# Choin_zlacza.net
KiCad netlist of a schematic drawn in Altium Designer
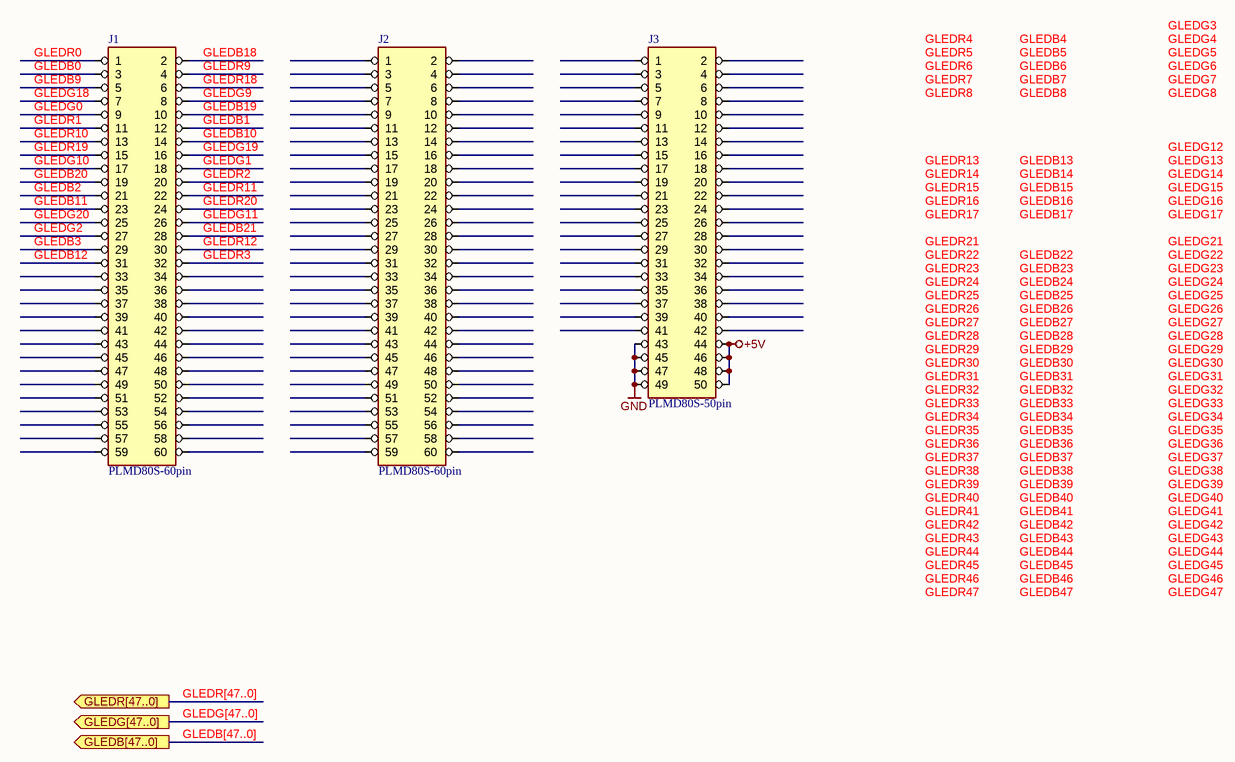
[diagram p0: Choin_zlacza.SchDoc]

(export (version "E")
  (design (tool "Eeschema 10.0.6"))
  (components
    (comp (ref "J1")
      (value "PLMD80S-60pin")
      (footprint "PLMD60S")
      (libsource (lib "Parts") (part "HEADER30X2"))
    )
    (comp (ref "J2")
      (value "PLMD80S-60pin")
      (footprint "PLMD60S")
      (libsource (lib "Parts") (part "HEADER30X2"))
    )
    (comp (ref "J3")
      (value "PLMD80S-50pin")
      (footprint "PLMD50S")
      (libsource (lib "Parts") (part "HEADER25X2"))
    )
  )
  (nets
    (net (code "1") (name "+5V") (class "Default")
      (node (ref "J3") (pin "44") (pinfunction "44_44") (pintype "passive"))
      (node (ref "J3") (pin "46") (pinfunction "46_46") (pintype "passive"))
      (node (ref "J3") (pin "48") (pinfunction "48_48") (pintype "passive"))
      (node (ref "J3") (pin "50") (pinfunction "50_50") (pintype "passive"))
    )
    (net (code "2") (name "/GLEDB0") (class "Default")
      (node (ref "J1") (pin "3") (pinfunction "3_3") (pintype "passive"))
    )
    (net (code "3") (name "/GLEDB1") (class "Default")
      (node (ref "J1") (pin "12") (pinfunction "12_12") (pintype "passive"))
    )
    (net (code "4") (name "/GLEDB2") (class "Default")
      (node (ref "J1") (pin "21") (pinfunction "21_21") (pintype "passive"))
    )
    (net (code "5") (name "/GLEDB3") (class "Default")
      (node (ref "J1") (pin "29") (pinfunction "29_29") (pintype "passive"))
    )
    (net (code "11") (name "/GLEDB9") (class "Default")
      (node (ref "J1") (pin "5") (pinfunction "5_5") (pintype "passive"))
    )
    (net (code "12") (name "/GLEDB10") (class "Default")
      (node (ref "J1") (pin "14") (pinfunction "14_14") (pintype "passive"))
    )
    (net (code "13") (name "/GLEDB11") (class "Default")
      (node (ref "J1") (pin "23") (pinfunction "23_23") (pintype "passive"))
    )
    (net (code "14") (name "/GLEDB12") (class "Default")
      (node (ref "J1") (pin "31") (pinfunction "31_31") (pintype "passive"))
    )
    (net (code "20") (name "/GLEDB18") (class "Default")
      (node (ref "J1") (pin "2") (pinfunction "2_2") (pintype "passive"))
    )
    (net (code "21") (name "/GLEDB19") (class "Default")
      (node (ref "J1") (pin "10") (pinfunction "10_10") (pintype "passive"))
    )
    (net (code "22") (name "/GLEDB20") (class "Default")
      (node (ref "J1") (pin "19") (pinfunction "19_19") (pintype "passive"))
    )
    (net (code "23") (name "/GLEDB21") (class "Default")
      (node (ref "J1") (pin "28") (pinfunction "28_28") (pintype "passive"))
    )
    (net (code "51") (name "/GLEDG0") (class "Default")
      (node (ref "J1") (pin "9") (pinfunction "9_9") (pintype "passive"))
    )
    (net (code "52") (name "/GLEDG1") (class "Default")
      (node (ref "J1") (pin "18") (pinfunction "18_18") (pintype "passive"))
    )
    (net (code "53") (name "/GLEDG2") (class "Default")
      (node (ref "J1") (pin "27") (pinfunction "27_27") (pintype "passive"))
    )
    (net (code "60") (name "/GLEDG9") (class "Default")
      (node (ref "J1") (pin "8") (pinfunction "8_8") (pintype "passive"))
    )
    (net (code "61") (name "/GLEDG10") (class "Default")
      (node (ref "J1") (pin "17") (pinfunction "17_17") (pintype "passive"))
    )
    (net (code "62") (name "/GLEDG11") (class "Default")
      (node (ref "J1") (pin "26") (pinfunction "26_26") (pintype "passive"))
    )
    (net (code "69") (name "/GLEDG18") (class "Default")
      (node (ref "J1") (pin "7") (pinfunction "7_7") (pintype "passive"))
    )
    (net (code "70") (name "/GLEDG19") (class "Default")
      (node (ref "J1") (pin "16") (pinfunction "16_16") (pintype "passive"))
    )
    (net (code "71") (name "/GLEDG20") (class "Default")
      (node (ref "J1") (pin "25") (pinfunction "25_25") (pintype "passive"))
    )
    (net (code "100") (name "/GLEDR0") (class "Default")
      (node (ref "J1") (pin "1") (pinfunction "1_1") (pintype "passive"))
    )
    (net (code "101") (name "/GLEDR1") (class "Default")
      (node (ref "J1") (pin "11") (pinfunction "11_11") (pintype "passive"))
    )
    (net (code "102") (name "/GLEDR2") (class "Default")
      (node (ref "J1") (pin "20") (pinfunction "20_20") (pintype "passive"))
    )
    (net (code "103") (name "/GLEDR3") (class "Default")
      (node (ref "J1") (pin "32") (pinfunction "32_32") (pintype "passive"))
    )
    (net (code "109") (name "/GLEDR9") (class "Default")
      (node (ref "J1") (pin "4") (pinfunction "4_4") (pintype "passive"))
    )
    (net (code "110") (name "/GLEDR10") (class "Default")
      (node (ref "J1") (pin "13") (pinfunction "13_13") (pintype "passive"))
    )
    (net (code "111") (name "/GLEDR11") (class "Default")
      (node (ref "J1") (pin "22") (pinfunction "22_22") (pintype "passive"))
    )
    (net (code "112") (name "/GLEDR12") (class "Default")
      (node (ref "J1") (pin "30") (pinfunction "30_30") (pintype "passive"))
    )
    (net (code "118") (name "/GLEDR18") (class "Default")
      (node (ref "J1") (pin "6") (pinfunction "6_6") (pintype "passive"))
    )
    (net (code "119") (name "/GLEDR19") (class "Default")
      (node (ref "J1") (pin "15") (pinfunction "15_15") (pintype "passive"))
    )
    (net (code "120") (name "/GLEDR20") (class "Default")
      (node (ref "J1") (pin "24") (pinfunction "24_24") (pintype "passive"))
    )
    (net (code "149") (name "GND") (class "Default")
      (node (ref "J3") (pin "43") (pinfunction "43_43") (pintype "passive"))
      (node (ref "J3") (pin "45") (pinfunction "45_45") (pintype "passive"))
      (node (ref "J3") (pin "47") (pinfunction "47_47") (pintype "passive"))
      (node (ref "J3") (pin "49") (pinfunction "49_49") (pintype "passive"))
    )
    (net (code "150") (name "unconnected-(J1-Pad33)") (class "Default")
      (node (ref "J1") (pin "33") (pinfunction "33_33") (pintype "passive"))
    )
    (net (code "151") (name "unconnected-(J1-Pad34)") (class "Default")
      (node (ref "J1") (pin "34") (pinfunction "34_34") (pintype "passive"))
    )
    (net (code "152") (name "unconnected-(J1-Pad35)") (class "Default")
      (node (ref "J1") (pin "35") (pinfunction "35_35") (pintype "passive"))
    )
    (net (code "153") (name "unconnected-(J1-Pad36)") (class "Default")
      (node (ref "J1") (pin "36") (pinfunction "36_36") (pintype "passive"))
    )
    (net (code "154") (name "unconnected-(J1-Pad37)") (class "Default")
      (node (ref "J1") (pin "37") (pinfunction "37_37") (pintype "passive"))
    )
    (net (code "155") (name "unconnected-(J1-Pad38)") (class "Default")
      (node (ref "J1") (pin "38") (pinfunction "38_38") (pintype "passive"))
    )
    (net (code "156") (name "unconnected-(J1-Pad39)") (class "Default")
      (node (ref "J1") (pin "39") (pinfunction "39_39") (pintype "passive"))
    )
    (net (code "157") (name "unconnected-(J1-Pad40)") (class "Default")
      (node (ref "J1") (pin "40") (pinfunction "40_40") (pintype "passive"))
    )
    (net (code "158") (name "unconnected-(J1-Pad41)") (class "Default")
      (node (ref "J1") (pin "41") (pinfunction "41_41") (pintype "passive"))
    )
    (net (code "159") (name "unconnected-(J1-Pad42)") (class "Default")
      (node (ref "J1") (pin "42") (pinfunction "42_42") (pintype "passive"))
    )
    (net (code "160") (name "unconnected-(J1-Pad43)") (class "Default")
      (node (ref "J1") (pin "43") (pinfunction "43_43") (pintype "passive"))
    )
    (net (code "161") (name "unconnected-(J1-Pad44)") (class "Default")
      (node (ref "J1") (pin "44") (pinfunction "44_44") (pintype "passive"))
    )
    (net (code "162") (name "unconnected-(J1-Pad45)") (class "Default")
      (node (ref "J1") (pin "45") (pinfunction "45_45") (pintype "passive"))
    )
    (net (code "163") (name "unconnected-(J1-Pad46)") (class "Default")
      (node (ref "J1") (pin "46") (pinfunction "46_46") (pintype "passive"))
    )
    (net (code "164") (name "unconnected-(J1-Pad47)") (class "Default")
      (node (ref "J1") (pin "47") (pinfunction "47_47") (pintype "passive"))
    )
    (net (code "165") (name "unconnected-(J1-Pad48)") (class "Default")
      (node (ref "J1") (pin "48") (pinfunction "48_48") (pintype "passive"))
    )
    (net (code "166") (name "unconnected-(J1-Pad49)") (class "Default")
      (node (ref "J1") (pin "49") (pinfunction "49_49") (pintype "passive"))
    )
    (net (code "167") (name "unconnected-(J1-Pad50)") (class "Default")
      (node (ref "J1") (pin "50") (pinfunction "50_50") (pintype "passive"))
    )
    (net (code "168") (name "unconnected-(J1-Pad51)") (class "Default")
      (node (ref "J1") (pin "51") (pinfunction "51_51") (pintype "passive"))
    )
    (net (code "169") (name "unconnected-(J1-Pad52)") (class "Default")
      (node (ref "J1") (pin "52") (pinfunction "52_52") (pintype "passive"))
    )
    (net (code "170") (name "unconnected-(J1-Pad53)") (class "Default")
      (node (ref "J1") (pin "53") (pinfunction "53_53") (pintype "passive"))
    )
    (net (code "171") (name "unconnected-(J1-Pad54)") (class "Default")
      (node (ref "J1") (pin "54") (pinfunction "54_54") (pintype "passive"))
    )
    (net (code "172") (name "unconnected-(J1-Pad55)") (class "Default")
      (node (ref "J1") (pin "55") (pinfunction "55_55") (pintype "passive"))
    )
    (net (code "173") (name "unconnected-(J1-Pad56)") (class "Default")
      (node (ref "J1") (pin "56") (pinfunction "56_56") (pintype "passive"))
    )
    (net (code "174") (name "unconnected-(J1-Pad57)") (class "Default")
      (node (ref "J1") (pin "57") (pinfunction "57_57") (pintype "passive"))
    )
    (net (code "175") (name "unconnected-(J1-Pad58)") (class "Default")
      (node (ref "J1") (pin "58") (pinfunction "58_58") (pintype "passive"))
    )
    (net (code "176") (name "unconnected-(J1-Pad59)") (class "Default")
      (node (ref "J1") (pin "59") (pinfunction "59_59") (pintype "passive"))
    )
    (net (code "177") (name "unconnected-(J1-Pad60)") (class "Default")
      (node (ref "J1") (pin "60") (pinfunction "60_60") (pintype "passive"))
    )
    (net (code "178") (name "unconnected-(J2-Pad1)") (class "Default")
      (node (ref "J2") (pin "1") (pinfunction "1_1") (pintype "passive"))
    )
    (net (code "179") (name "unconnected-(J2-Pad2)") (class "Default")
      (node (ref "J2") (pin "2") (pinfunction "2_2") (pintype "passive"))
    )
    (net (code "180") (name "unconnected-(J2-Pad3)") (class "Default")
      (node (ref "J2") (pin "3") (pinfunction "3_3") (pintype "passive"))
    )
    (net (code "181") (name "unconnected-(J2-Pad4)") (class "Default")
      (node (ref "J2") (pin "4") (pinfunction "4_4") (pintype "passive"))
    )
    (net (code "182") (name "unconnected-(J2-Pad5)") (class "Default")
      (node (ref "J2") (pin "5") (pinfunction "5_5") (pintype "passive"))
    )
    (net (code "183") (name "unconnected-(J2-Pad6)") (class "Default")
      (node (ref "J2") (pin "6") (pinfunction "6_6") (pintype "passive"))
    )
    (net (code "184") (name "unconnected-(J2-Pad7)") (class "Default")
      (node (ref "J2") (pin "7") (pinfunction "7_7") (pintype "passive"))
    )
    (net (code "185") (name "unconnected-(J2-Pad8)") (class "Default")
      (node (ref "J2") (pin "8") (pinfunction "8_8") (pintype "passive"))
    )
    (net (code "186") (name "unconnected-(J2-Pad9)") (class "Default")
      (node (ref "J2") (pin "9") (pinfunction "9_9") (pintype "passive"))
    )
    (net (code "187") (name "unconnected-(J2-Pad10)") (class "Default")
      (node (ref "J2") (pin "10") (pinfunction "10_10") (pintype "passive"))
    )
    (net (code "188") (name "unconnected-(J2-Pad11)") (class "Default")
      (node (ref "J2") (pin "11") (pinfunction "11_11") (pintype "passive"))
    )
    (net (code "189") (name "unconnected-(J2-Pad12)") (class "Default")
      (node (ref "J2") (pin "12") (pinfunction "12_12") (pintype "passive"))
    )
    (net (code "190") (name "unconnected-(J2-Pad13)") (class "Default")
      (node (ref "J2") (pin "13") (pinfunction "13_13") (pintype "passive"))
    )
    (net (code "191") (name "unconnected-(J2-Pad14)") (class "Default")
      (node (ref "J2") (pin "14") (pinfunction "14_14") (pintype "passive"))
    )
    (net (code "192") (name "unconnected-(J2-Pad15)") (class "Default")
      (node (ref "J2") (pin "15") (pinfunction "15_15") (pintype "passive"))
    )
    (net (code "193") (name "unconnected-(J2-Pad16)") (class "Default")
      (node (ref "J2") (pin "16") (pinfunction "16_16") (pintype "passive"))
    )
    (net (code "194") (name "unconnected-(J2-Pad17)") (class "Default")
      (node (ref "J2") (pin "17") (pinfunction "17_17") (pintype "passive"))
    )
    (net (code "195") (name "unconnected-(J2-Pad18)") (class "Default")
      (node (ref "J2") (pin "18") (pinfunction "18_18") (pintype "passive"))
    )
    (net (code "196") (name "unconnected-(J2-Pad19)") (class "Default")
      (node (ref "J2") (pin "19") (pinfunction "19_19") (pintype "passive"))
    )
    (net (code "197") (name "unconnected-(J2-Pad20)") (class "Default")
      (node (ref "J2") (pin "20") (pinfunction "20_20") (pintype "passive"))
    )
    (net (code "198") (name "unconnected-(J2-Pad21)") (class "Default")
      (node (ref "J2") (pin "21") (pinfunction "21_21") (pintype "passive"))
    )
    (net (code "199") (name "unconnected-(J2-Pad22)") (class "Default")
      (node (ref "J2") (pin "22") (pinfunction "22_22") (pintype "passive"))
    )
    (net (code "200") (name "unconnected-(J2-Pad23)") (class "Default")
      (node (ref "J2") (pin "23") (pinfunction "23_23") (pintype "passive"))
    )
    (net (code "201") (name "unconnected-(J2-Pad24)") (class "Default")
      (node (ref "J2") (pin "24") (pinfunction "24_24") (pintype "passive"))
    )
    (net (code "202") (name "unconnected-(J2-Pad25)") (class "Default")
      (node (ref "J2") (pin "25") (pinfunction "25_25") (pintype "passive"))
    )
    (net (code "203") (name "unconnected-(J2-Pad26)") (class "Default")
      (node (ref "J2") (pin "26") (pinfunction "26_26") (pintype "passive"))
    )
    (net (code "204") (name "unconnected-(J2-Pad27)") (class "Default")
      (node (ref "J2") (pin "27") (pinfunction "27_27") (pintype "passive"))
    )
    (net (code "205") (name "unconnected-(J2-Pad28)") (class "Default")
      (node (ref "J2") (pin "28") (pinfunction "28_28") (pintype "passive"))
    )
    (net (code "206") (name "unconnected-(J2-Pad29)") (class "Default")
      (node (ref "J2") (pin "29") (pinfunction "29_29") (pintype "passive"))
    )
    (net (code "207") (name "unconnected-(J2-Pad30)") (class "Default")
      (node (ref "J2") (pin "30") (pinfunction "30_30") (pintype "passive"))
    )
    (net (code "208") (name "unconnected-(J2-Pad31)") (class "Default")
      (node (ref "J2") (pin "31") (pinfunction "31_31") (pintype "passive"))
    )
    (net (code "209") (name "unconnected-(J2-Pad32)") (class "Default")
      (node (ref "J2") (pin "32") (pinfunction "32_32") (pintype "passive"))
    )
    (net (code "210") (name "unconnected-(J2-Pad33)") (class "Default")
      (node (ref "J2") (pin "33") (pinfunction "33_33") (pintype "passive"))
    )
    (net (code "211") (name "unconnected-(J2-Pad34)") (class "Default")
      (node (ref "J2") (pin "34") (pinfunction "34_34") (pintype "passive"))
    )
    (net (code "212") (name "unconnected-(J2-Pad35)") (class "Default")
      (node (ref "J2") (pin "35") (pinfunction "35_35") (pintype "passive"))
    )
    (net (code "213") (name "unconnected-(J2-Pad36)") (class "Default")
      (node (ref "J2") (pin "36") (pinfunction "36_36") (pintype "passive"))
    )
    (net (code "214") (name "unconnected-(J2-Pad37)") (class "Default")
      (node (ref "J2") (pin "37") (pinfunction "37_37") (pintype "passive"))
    )
    (net (code "215") (name "unconnected-(J2-Pad38)") (class "Default")
      (node (ref "J2") (pin "38") (pinfunction "38_38") (pintype "passive"))
    )
    (net (code "216") (name "unconnected-(J2-Pad39)") (class "Default")
      (node (ref "J2") (pin "39") (pinfunction "39_39") (pintype "passive"))
    )
    (net (code "217") (name "unconnected-(J2-Pad40)") (class "Default")
      (node (ref "J2") (pin "40") (pinfunction "40_40") (pintype "passive"))
    )
    (net (code "218") (name "unconnected-(J2-Pad41)") (class "Default")
      (node (ref "J2") (pin "41") (pinfunction "41_41") (pintype "passive"))
    )
    (net (code "219") (name "unconnected-(J2-Pad42)") (class "Default")
      (node (ref "J2") (pin "42") (pinfunction "42_42") (pintype "passive"))
    )
    (net (code "220") (name "unconnected-(J2-Pad43)") (class "Default")
      (node (ref "J2") (pin "43") (pinfunction "43_43") (pintype "passive"))
    )
    (net (code "221") (name "unconnected-(J2-Pad44)") (class "Default")
      (node (ref "J2") (pin "44") (pinfunction "44_44") (pintype "passive"))
    )
    (net (code "222") (name "unconnected-(J2-Pad45)") (class "Default")
      (node (ref "J2") (pin "45") (pinfunction "45_45") (pintype "passive"))
    )
    (net (code "223") (name "unconnected-(J2-Pad46)") (class "Default")
      (node (ref "J2") (pin "46") (pinfunction "46_46") (pintype "passive"))
    )
    (net (code "224") (name "unconnected-(J2-Pad47)") (class "Default")
      (node (ref "J2") (pin "47") (pinfunction "47_47") (pintype "passive"))
    )
    (net (code "225") (name "unconnected-(J2-Pad48)") (class "Default")
      (node (ref "J2") (pin "48") (pinfunction "48_48") (pintype "passive"))
    )
    (net (code "226") (name "unconnected-(J2-Pad49)") (class "Default")
      (node (ref "J2") (pin "49") (pinfunction "49_49") (pintype "passive"))
    )
    (net (code "227") (name "unconnected-(J2-Pad50)") (class "Default")
      (node (ref "J2") (pin "50") (pinfunction "50_50") (pintype "passive"))
    )
    (net (code "228") (name "unconnected-(J2-Pad51)") (class "Default")
      (node (ref "J2") (pin "51") (pinfunction "51_51") (pintype "passive"))
    )
    (net (code "229") (name "unconnected-(J2-Pad52)") (class "Default")
      (node (ref "J2") (pin "52") (pinfunction "52_52") (pintype "passive"))
    )
    (net (code "230") (name "unconnected-(J2-Pad53)") (class "Default")
      (node (ref "J2") (pin "53") (pinfunction "53_53") (pintype "passive"))
    )
    (net (code "231") (name "unconnected-(J2-Pad54)") (class "Default")
      (node (ref "J2") (pin "54") (pinfunction "54_54") (pintype "passive"))
    )
    (net (code "232") (name "unconnected-(J2-Pad55)") (class "Default")
      (node (ref "J2") (pin "55") (pinfunction "55_55") (pintype "passive"))
    )
    (net (code "233") (name "unconnected-(J2-Pad56)") (class "Default")
      (node (ref "J2") (pin "56") (pinfunction "56_56") (pintype "passive"))
    )
    (net (code "234") (name "unconnected-(J2-Pad57)") (class "Default")
      (node (ref "J2") (pin "57") (pinfunction "57_57") (pintype "passive"))
    )
    (net (code "235") (name "unconnected-(J2-Pad58)") (class "Default")
      (node (ref "J2") (pin "58") (pinfunction "58_58") (pintype "passive"))
    )
    (net (code "236") (name "unconnected-(J2-Pad59)") (class "Default")
      (node (ref "J2") (pin "59") (pinfunction "59_59") (pintype "passive"))
    )
    (net (code "237") (name "unconnected-(J2-Pad60)") (class "Default")
      (node (ref "J2") (pin "60") (pinfunction "60_60") (pintype "passive"))
    )
    (net (code "238") (name "unconnected-(J3-Pad1)") (class "Default")
      (node (ref "J3") (pin "1") (pinfunction "1_1") (pintype "passive"))
    )
    (net (code "239") (name "unconnected-(J3-Pad2)") (class "Default")
      (node (ref "J3") (pin "2") (pinfunction "2_2") (pintype "passive"))
    )
    (net (code "240") (name "unconnected-(J3-Pad3)") (class "Default")
      (node (ref "J3") (pin "3") (pinfunction "3_3") (pintype "passive"))
    )
    (net (code "241") (name "unconnected-(J3-Pad4)") (class "Default")
      (node (ref "J3") (pin "4") (pinfunction "4_4") (pintype "passive"))
    )
    (net (code "242") (name "unconnected-(J3-Pad5)") (class "Default")
      (node (ref "J3") (pin "5") (pinfunction "5_5") (pintype "passive"))
    )
    (net (code "243") (name "unconnected-(J3-Pad6)") (class "Default")
      (node (ref "J3") (pin "6") (pinfunction "6_6") (pintype "passive"))
    )
    (net (code "244") (name "unconnected-(J3-Pad7)") (class "Default")
      (node (ref "J3") (pin "7") (pinfunction "7_7") (pintype "passive"))
    )
    (net (code "245") (name "unconnected-(J3-Pad8)") (class "Default")
      (node (ref "J3") (pin "8") (pinfunction "8_8") (pintype "passive"))
    )
    (net (code "246") (name "unconnected-(J3-Pad9)") (class "Default")
      (node (ref "J3") (pin "9") (pinfunction "9_9") (pintype "passive"))
    )
    (net (code "247") (name "unconnected-(J3-Pad10)") (class "Default")
      (node (ref "J3") (pin "10") (pinfunction "10_10") (pintype "passive"))
    )
    (net (code "248") (name "unconnected-(J3-Pad11)") (class "Default")
      (node (ref "J3") (pin "11") (pinfunction "11_11") (pintype "passive"))
    )
    (net (code "249") (name "unconnected-(J3-Pad12)") (class "Default")
      (node (ref "J3") (pin "12") (pinfunction "12_12") (pintype "passive"))
    )
    (net (code "250") (name "unconnected-(J3-Pad13)") (class "Default")
      (node (ref "J3") (pin "13") (pinfunction "13_13") (pintype "passive"))
    )
    (net (code "251") (name "unconnected-(J3-Pad14)") (class "Default")
      (node (ref "J3") (pin "14") (pinfunction "14_14") (pintype "passive"))
    )
    (net (code "252") (name "unconnected-(J3-Pad15)") (class "Default")
      (node (ref "J3") (pin "15") (pinfunction "15_15") (pintype "passive"))
    )
    (net (code "253") (name "unconnected-(J3-Pad16)") (class "Default")
      (node (ref "J3") (pin "16") (pinfunction "16_16") (pintype "passive"))
    )
    (net (code "254") (name "unconnected-(J3-Pad17)") (class "Default")
      (node (ref "J3") (pin "17") (pinfunction "17_17") (pintype "passive"))
    )
    (net (code "255") (name "unconnected-(J3-Pad18)") (class "Default")
      (node (ref "J3") (pin "18") (pinfunction "18_18") (pintype "passive"))
    )
    (net (code "256") (name "unconnected-(J3-Pad19)") (class "Default")
      (node (ref "J3") (pin "19") (pinfunction "19_19") (pintype "passive"))
    )
    (net (code "257") (name "unconnected-(J3-Pad20)") (class "Default")
      (node (ref "J3") (pin "20") (pinfunction "20_20") (pintype "passive"))
    )
    (net (code "258") (name "unconnected-(J3-Pad21)") (class "Default")
      (node (ref "J3") (pin "21") (pinfunction "21_21") (pintype "passive"))
    )
    (net (code "259") (name "unconnected-(J3-Pad22)") (class "Default")
      (node (ref "J3") (pin "22") (pinfunction "22_22") (pintype "passive"))
    )
    (net (code "260") (name "unconnected-(J3-Pad23)") (class "Default")
      (node (ref "J3") (pin "23") (pinfunction "23_23") (pintype "passive"))
    )
    (net (code "261") (name "unconnected-(J3-Pad24)") (class "Default")
      (node (ref "J3") (pin "24") (pinfunction "24_24") (pintype "passive"))
    )
    (net (code "262") (name "unconnected-(J3-Pad25)") (class "Default")
      (node (ref "J3") (pin "25") (pinfunction "25_25") (pintype "passive"))
    )
    (net (code "263") (name "unconnected-(J3-Pad26)") (class "Default")
      (node (ref "J3") (pin "26") (pinfunction "26_26") (pintype "passive"))
    )
    (net (code "264") (name "unconnected-(J3-Pad27)") (class "Default")
      (node (ref "J3") (pin "27") (pinfunction "27_27") (pintype "passive"))
    )
    (net (code "265") (name "unconnected-(J3-Pad28)") (class "Default")
      (node (ref "J3") (pin "28") (pinfunction "28_28") (pintype "passive"))
    )
    (net (code "266") (name "unconnected-(J3-Pad29)") (class "Default")
      (node (ref "J3") (pin "29") (pinfunction "29_29") (pintype "passive"))
    )
    (net (code "267") (name "unconnected-(J3-Pad30)") (class "Default")
      (node (ref "J3") (pin "30") (pinfunction "30_30") (pintype "passive"))
    )
    (net (code "268") (name "unconnected-(J3-Pad31)") (class "Default")
      (node (ref "J3") (pin "31") (pinfunction "31_31") (pintype "passive"))
    )
    (net (code "269") (name "unconnected-(J3-Pad32)") (class "Default")
      (node (ref "J3") (pin "32") (pinfunction "32_32") (pintype "passive"))
    )
    (net (code "270") (name "unconnected-(J3-Pad33)") (class "Default")
      (node (ref "J3") (pin "33") (pinfunction "33_33") (pintype "passive"))
    )
    (net (code "271") (name "unconnected-(J3-Pad34)") (class "Default")
      (node (ref "J3") (pin "34") (pinfunction "34_34") (pintype "passive"))
    )
    (net (code "272") (name "unconnected-(J3-Pad35)") (class "Default")
      (node (ref "J3") (pin "35") (pinfunction "35_35") (pintype "passive"))
    )
    (net (code "273") (name "unconnected-(J3-Pad36)") (class "Default")
      (node (ref "J3") (pin "36") (pinfunction "36_36") (pintype "passive"))
    )
    (net (code "274") (name "unconnected-(J3-Pad37)") (class "Default")
      (node (ref "J3") (pin "37") (pinfunction "37_37") (pintype "passive"))
    )
    (net (code "275") (name "unconnected-(J3-Pad38)") (class "Default")
      (node (ref "J3") (pin "38") (pinfunction "38_38") (pintype "passive"))
    )
    (net (code "276") (name "unconnected-(J3-Pad39)") (class "Default")
      (node (ref "J3") (pin "39") (pinfunction "39_39") (pintype "passive"))
    )
    (net (code "277") (name "unconnected-(J3-Pad40)") (class "Default")
      (node (ref "J3") (pin "40") (pinfunction "40_40") (pintype "passive"))
    )
    (net (code "278") (name "unconnected-(J3-Pad41)") (class "Default")
      (node (ref "J3") (pin "41") (pinfunction "41_41") (pintype "passive"))
    )
    (net (code "279") (name "unconnected-(J3-Pad42)") (class "Default")
      (node (ref "J3") (pin "42") (pinfunction "42_42") (pintype "passive"))
    )
  )
)
